# mx8m_cfg.net
KiCad netlist of a schematic drawn in Altium Designer
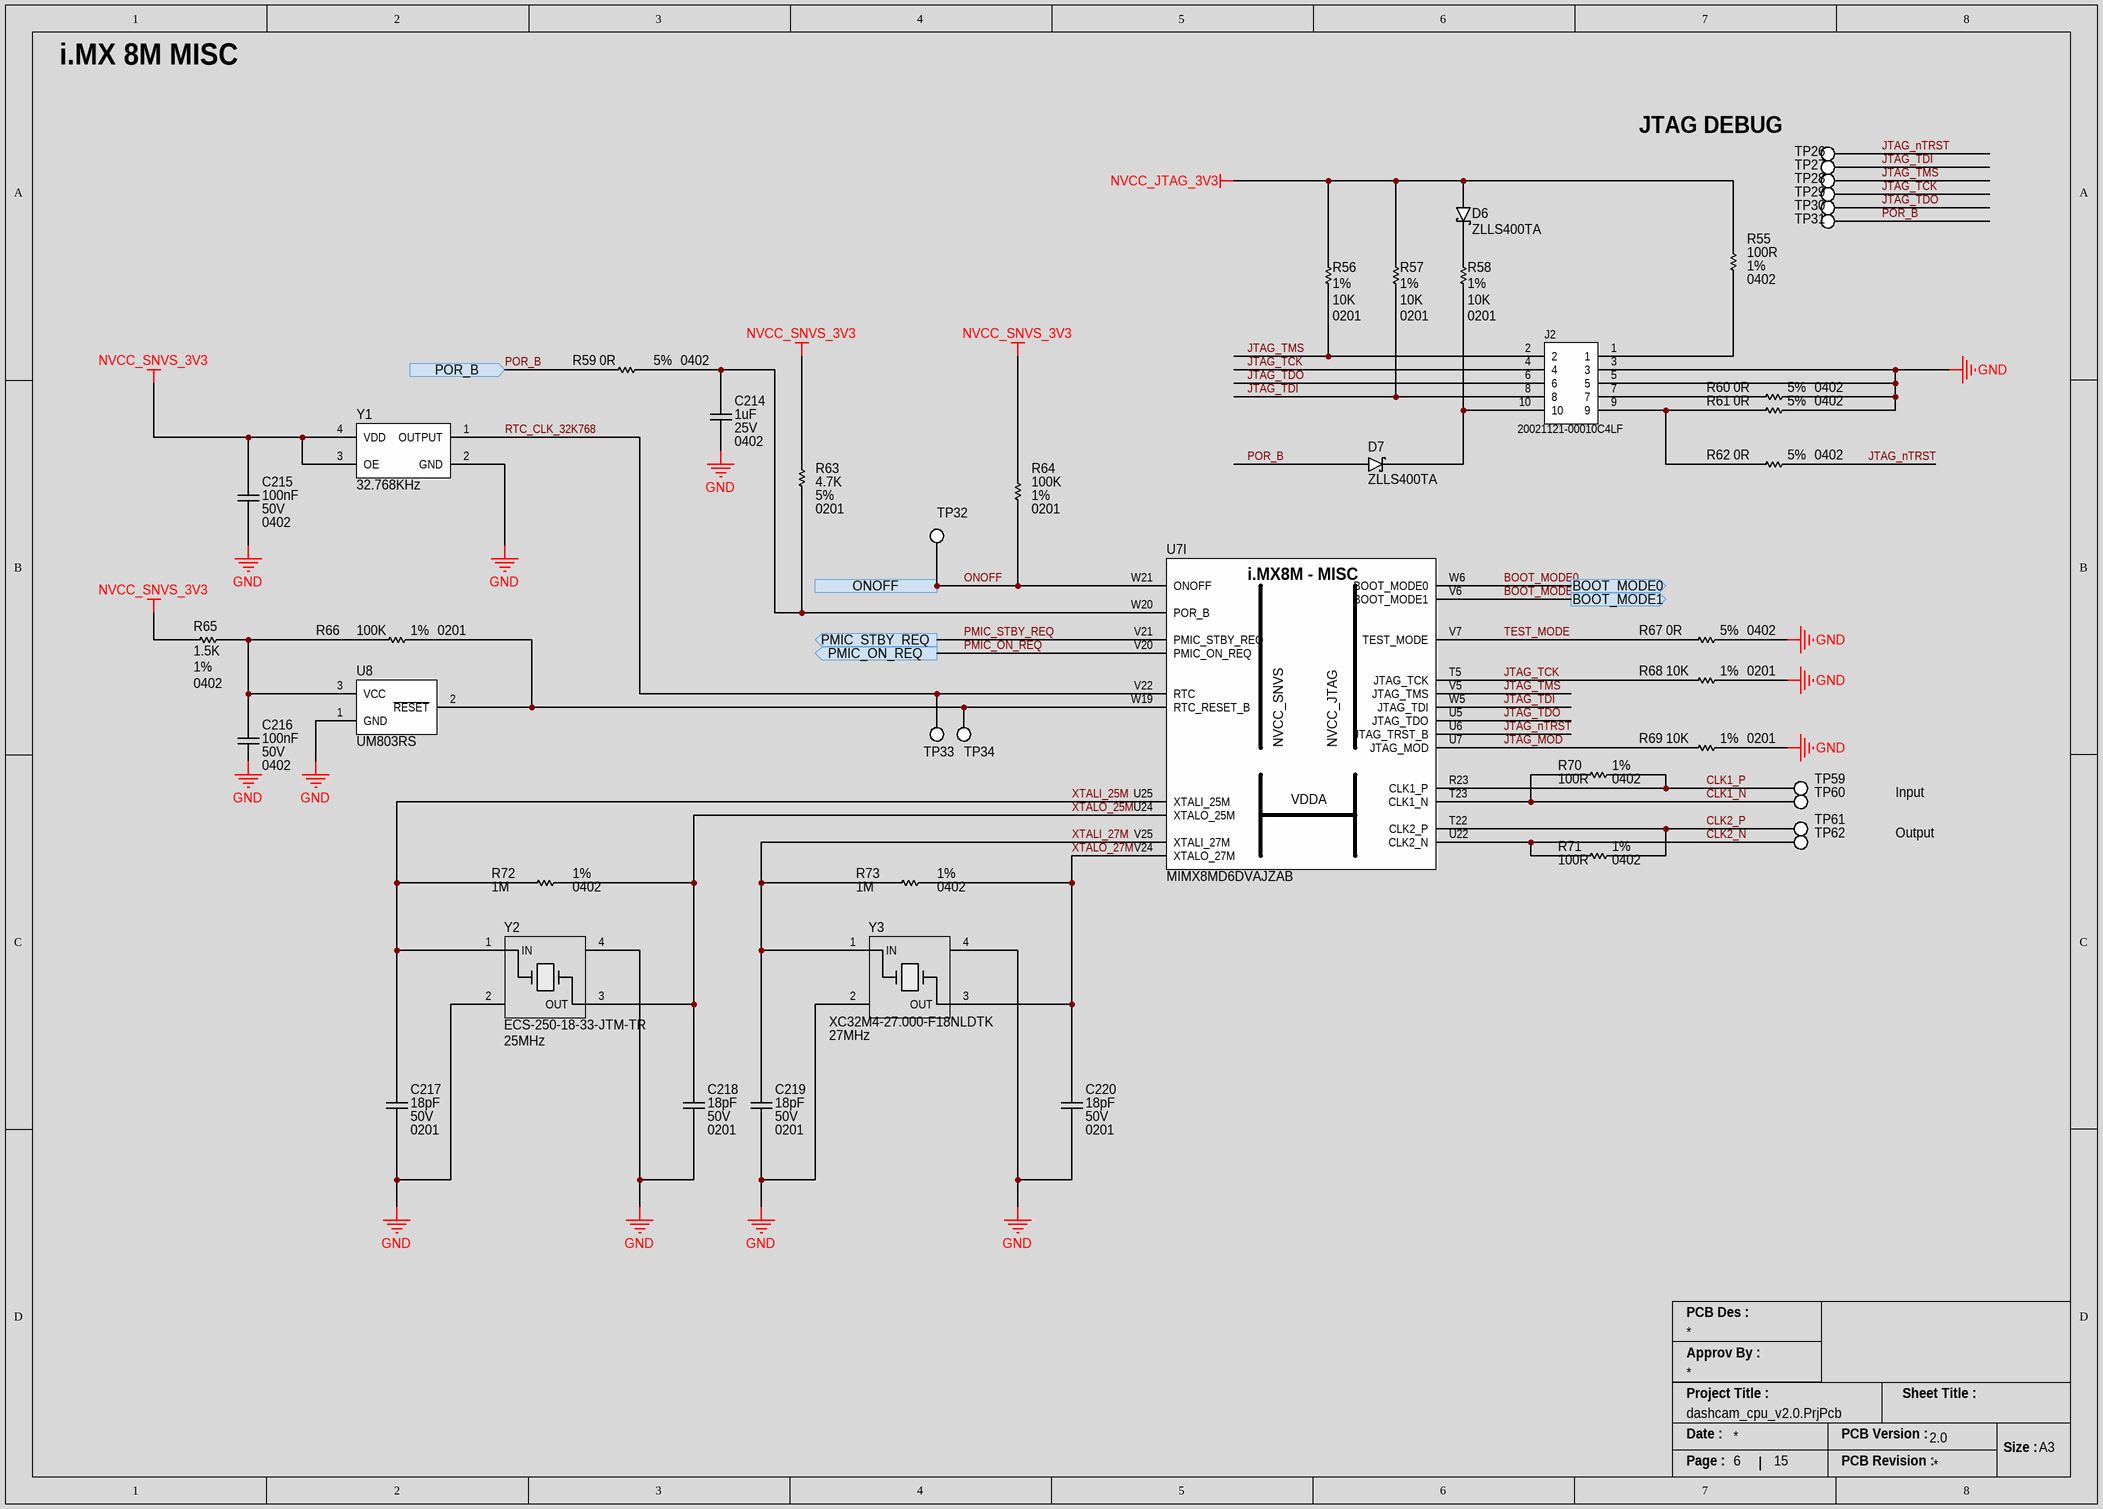
[diagram p0: mx8m_cfg.SchDoc]

(export (version "E")
  (design (tool "Eeschema 10.0.6"))
  (components
    (comp (ref "C214")
      (value "GRM155R61E105KA12D")
      (footprint "CAP_0402_CAPC1005X05N")
      (description "Multilayer Ceramic Capacitor, 1 uF, 25 V, ± 10%, X5R, 0402 [1005 Metric]")
      (fields
        (field (name "MANUFACTURER") "Murata")
        (field (name "TOLERANCE") "10%")
        (field (name "VOLTAGE RATING") "25V")
        (field (name "CAPACITANCE") "1uF")
        (field (name "CASE CODE (IMPERIAL)") "0402")
      )
      (libsource (lib "Electronic Devices_LIB") (part "CAP_1UF_25V_X5R_0402"))
    )
    (comp (ref "C215")
      (value "GRM155R71H104KE14D")
      (footprint "CAP_0402_CAPC1005X05N")
      (description "Multilayer Ceramic Capacitor, 0.1 uF, 16 V, ± 10%, X7R, 0402 [1005 Metric]")
      (fields
        (field (name "MANUFACTURER") "Murata")
        (field (name "TOLERANCE") "10%")
        (field (name "VOLTAGE RATING") "50V")
        (field (name "CAPACITANCE") "100nF")
        (field (name "CASE/PACKAGE") "0402")
      )
      (libsource (lib "Electronic Devices_LIB") (part "CAP_100NF_50V_X7R_0402"))
    )
    (comp (ref "C216")
      (value "GRM155R71H104KE14D")
      (footprint "CAP_0402_CAPC1005X05N")
      (description "Multilayer Ceramic Capacitor, 0.1 uF, 16 V, ± 10%, X7R, 0402 [1005 Metric]")
      (fields
        (field (name "MANUFACTURER") "Murata")
        (field (name "TOLERANCE") "10%")
        (field (name "VOLTAGE RATING") "50V")
        (field (name "CAPACITANCE") "100nF")
        (field (name "CASE/PACKAGE") "0402")
      )
      (libsource (lib "Electronic Devices_LIB") (part "CAP_100NF_50V_X7R_0402"))
    )
    (comp (ref "C217")
      (value "GRM0335C1H180JA01D")
      (footprint "CAP_0201_CAPC0603X03N")
      (description "Multilayer Ceramic Capacitor, 18 pF, 50 V, ± 5%, C0G (NP0), 0201 [0603 Metric]")
      (fields
        (field (name "MANUFACTURER") "Murata")
        (field (name "TOLERANCE") "5%")
        (field (name "CAPACITANCE") "18pF")
        (field (name "VOLTAGE RATING") "50V")
        (field (name "CASE/PACKAGE") "0201")
      )
      (libsource (lib "Electronic Devices_LIB") (part "CAP_18PF_50V_NP0_0201"))
    )
    (comp (ref "C218")
      (value "GRM0335C1H180JA01D")
      (footprint "CAP_0201_CAPC0603X03N")
      (description "Multilayer Ceramic Capacitor, 18 pF, 50 V, ± 5%, C0G (NP0), 0201 [0603 Metric]")
      (fields
        (field (name "MANUFACTURER") "Murata")
        (field (name "TOLERANCE") "5%")
        (field (name "CAPACITANCE") "18pF")
        (field (name "VOLTAGE RATING") "50V")
        (field (name "CASE/PACKAGE") "0201")
      )
      (libsource (lib "Electronic Devices_LIB") (part "CAP_18PF_50V_NP0_0201"))
    )
    (comp (ref "C219")
      (value "GRM0335C1H180JA01D")
      (footprint "CAP_0201_CAPC0603X03N")
      (description "Multilayer Ceramic Capacitor, 18 pF, 50 V, ± 5%, C0G (NP0), 0201 [0603 Metric]")
      (fields
        (field (name "MANUFACTURER") "Murata")
        (field (name "TOLERANCE") "5%")
        (field (name "CAPACITANCE") "18pF")
        (field (name "VOLTAGE RATING") "50V")
        (field (name "CASE/PACKAGE") "0201")
      )
      (libsource (lib "Electronic Devices_LIB") (part "CAP_18PF_50V_NP0_0201"))
    )
    (comp (ref "C220")
      (value "GRM0335C1H180JA01D")
      (footprint "CAP_0201_CAPC0603X03N")
      (description "Multilayer Ceramic Capacitor, 18 pF, 50 V, ± 5%, C0G (NP0), 0201 [0603 Metric]")
      (fields
        (field (name "MANUFACTURER") "Murata")
        (field (name "TOLERANCE") "5%")
        (field (name "CAPACITANCE") "18pF")
        (field (name "VOLTAGE RATING") "50V")
        (field (name "CASE/PACKAGE") "0201")
      )
      (libsource (lib "Electronic Devices_LIB") (part "CAP_18PF_50V_NP0_0201"))
    )
    (comp (ref "D6")
      (value "ZLLS400TA")
      (footprint "DIO_SOD2512X113N")
      (description "DIODE SCHOTTKY 40V 520MA SOD323")
      (fields (field (name "MANUFACTURER") "Diodes Zetex"))
      (libsource (lib "Electronic Devices_LIB") (part "DIO_SCTKY_40V_520mA_ZLLS400TA"))
    )
    (comp (ref "D7")
      (value "ZLLS400TA")
      (footprint "DIO_SOD2512X113N")
      (description "DIODE SCHOTTKY 40V 520MA SOD323")
      (fields (field (name "MANUFACTURER") "Diodes Zetex"))
      (libsource (lib "Electronic Devices_LIB") (part "DIO_SCTKY_40V_520mA_ZLLS400TA"))
    )
    (comp (ref "J2")
      (value "20021121-00010C4LF")
      (footprint "CONN_HDR_MALE_10P_2R")
      (description "Conn Unshrouded Header HDR 10 POS 1.27mm Solder ST Top Entry SMD Minitek127® T/R")
      (fields (field (name "MANUFACTURER") "Amphenol ICC / FCI"))
      (libsource (lib "Electronic Devices_LIB") (part "CONN_HEADER_MALE_10P_2R_1.27MM"))
    )
    (comp (ref "R55")
      (value "ERJ-2RKF1000X")
      (footprint "RES_0402_RESC1005X04N")
      (description "Resistor Thick Film 0402 100 Ohm 1% 1/10W 100ppm/C Molded SMD Punched Carrier T/R")
      (fields
        (field (name "MANUFACTURER") "Panasonic")
        (field (name "TOLERANCE") "1%")
        (field (name "RESISTANCE") "100R")
        (field (name "CASE/PACKAGE") "0402")
      )
      (libsource (lib "Electronic Devices_LIB") (part "RES_100R_1%_100mW_0402"))
    )
    (comp (ref "R56")
      (value "RC0201FR-0710KL")
      (footprint "RES_0201_RESC0603X02N")
      (description "SMD Chip Resistor, 10 kOhm, ± 1%, 50 mW, 0201 [0603 Metric], Thick Film, General Purpose")
      (fields
        (field (name "MANUFACTURER") "Yageo")
        (field (name "TOLERANCE") "1%")
        (field (name "RESISTANCE") "10K")
        (field (name "CASE CODE (IMPERIAL)") "0201")
      )
      (libsource (lib "Electronic Devices_LIB") (part "RES_10K_1/12W_1%_0201"))
    )
    (comp (ref "R57")
      (value "RC0201FR-0710KL")
      (footprint "RES_0201_RESC0603X02N")
      (description "SMD Chip Resistor, 10 kOhm, ± 1%, 50 mW, 0201 [0603 Metric], Thick Film, General Purpose")
      (fields
        (field (name "MANUFACTURER") "Yageo")
        (field (name "TOLERANCE") "1%")
        (field (name "RESISTANCE") "10K")
        (field (name "CASE CODE (IMPERIAL)") "0201")
      )
      (libsource (lib "Electronic Devices_LIB") (part "RES_10K_1/12W_1%_0201"))
    )
    (comp (ref "R58")
      (value "RC0201FR-0710KL")
      (footprint "RES_0201_RESC0603X02N")
      (description "SMD Chip Resistor, 10 kOhm, ± 1%, 50 mW, 0201 [0603 Metric], Thick Film, General Purpose")
      (fields
        (field (name "MANUFACTURER") "Yageo")
        (field (name "TOLERANCE") "1%")
        (field (name "RESISTANCE") "10K")
        (field (name "CASE CODE (IMPERIAL)") "0201")
      )
      (libsource (lib "Electronic Devices_LIB") (part "RES_10K_1/12W_1%_0201"))
    )
    (comp (ref "R59")
      (value "ERJ-2GE0R00X")
      (footprint "RES_0402_RESC1005X04N")
      (description "SMD Chip Resistor, Jumper, 0 ohm, 100 mW, 0402 [1005 Metric], Thick Film, General Purpose")
      (fields
        (field (name "MANUFACTURER") "Panasonic")
        (field (name "CASE CODE (IMPERIAL)") "0402")
        (field (name "TOLERANCE") "5%")
        (field (name "RESISTANCE") "0R")
      )
      (libsource (lib "Electronic Devices_LIB") (part "RES_0R_5%_100mW_0402"))
    )
    (comp (ref "R60")
      (value "ERJ-2GE0R00X")
      (footprint "RES_0402_RESC1005X04N")
      (description "SMD Chip Resistor, Jumper, 0 ohm, 100 mW, 0402 [1005 Metric], Thick Film, General Purpose")
      (fields
        (field (name "MANUFACTURER") "Panasonic")
        (field (name "CASE CODE (IMPERIAL)") "0402")
        (field (name "TOLERANCE") "5%")
        (field (name "RESISTANCE") "0R")
      )
      (libsource (lib "Electronic Devices_LIB") (part "RES_0R_5%_100mW_0402"))
    )
    (comp (ref "R61")
      (value "ERJ-2GE0R00X")
      (footprint "RES_0402_RESC1005X04N")
      (description "SMD Chip Resistor, Jumper, 0 ohm, 100 mW, 0402 [1005 Metric], Thick Film, General Purpose")
      (fields
        (field (name "MANUFACTURER") "Panasonic")
        (field (name "CASE CODE (IMPERIAL)") "0402")
        (field (name "TOLERANCE") "5%")
        (field (name "RESISTANCE") "0R")
      )
      (libsource (lib "Electronic Devices_LIB") (part "RES_0R_5%_100mW_0402"))
    )
    (comp (ref "R62")
      (value "ERJ-2GE0R00X")
      (footprint "RES_0402_RESC1005X04N")
      (description "SMD Chip Resistor, Jumper, 0 ohm, 100 mW, 0402 [1005 Metric], Thick Film, General Purpose")
      (fields
        (field (name "MANUFACTURER") "Panasonic")
        (field (name "CASE CODE (IMPERIAL)") "0402")
        (field (name "TOLERANCE") "5%")
        (field (name "RESISTANCE") "0R")
      )
      (libsource (lib "Electronic Devices_LIB") (part "RES_0R_5%_100mW_0402"))
    )
    (comp (ref "R63")
      (value "RK73B1HTTC472J")
      (footprint "RES_0201_RESC0603X02N")
      (description "Res Thick Film 0201 4.7K Ohm 5% 0.05W(1/20W) ±200ppm/C Pad SMD Automotive T/R")
      (fields
        (field (name "MANUFACTURER") "KOA Speer")
        (field (name "TOLERANCE") "5%")
        (field (name "RESISTANCE") "4.7K")
        (field (name "CASE/PACKAGE") "0201")
      )
      (libsource (lib "Electronic Devices_LIB") (part "RES_4.7K_5%_50mW_0201"))
    )
    (comp (ref "R64")
      (value "RC0201FR-07100KL")
      (footprint "RES_0201_RESC0603X02N")
      (description "SMD Chip Resistor, 100 kOhm, ± 1%, 50 mW, 0201 [0603 Metric], Thick Film, General Purpose")
      (fields
        (field (name "MANUFACTURER") "Yageo")
        (field (name "RESISTANCE") "100K")
        (field (name "TOLERANCE") "1%")
        (field (name "CASE/PACKAGE") "0201")
      )
      (libsource (lib "Electronic Devices_LIB") (part "RES_100K_1%_50mW_0201"))
    )
    (comp (ref "R65")
      (value "CR0402-FX-1501GLF")
      (footprint "RES_0402_RESC1005X04N")
      (description "Res Thick Film 0402 1.5K Ohm 1% 1/16W ±100ppm/°C Molded SMD SMD Paper Tape on Plastic Reel")
      (fields
        (field (name "MANUFACTURER") "Bourns")
        (field (name "RESISTANCE") "1.5K")
        (field (name "TOLERANCE") "1%")
        (field (name "CASE/PACKAGE") "0402")
      )
      (libsource (lib "Electronic Devices_LIB") (part "RES_1.5K_1%_63mW_0402"))
    )
    (comp (ref "R66")
      (value "RC0201FR-07100KL")
      (footprint "RES_0201_RESC0603X02N")
      (description "SMD Chip Resistor, 100 kOhm, ± 1%, 50 mW, 0201 [0603 Metric], Thick Film, General Purpose")
      (fields
        (field (name "MANUFACTURER") "Yageo")
        (field (name "RESISTANCE") "100K")
        (field (name "TOLERANCE") "1%")
        (field (name "CASE/PACKAGE") "0201")
      )
      (libsource (lib "Electronic Devices_LIB") (part "RES_100K_1%_50mW_0201"))
    )
    (comp (ref "R67")
      (value "ERJ-2GE0R00X")
      (footprint "RES_0402_RESC1005X04N")
      (description "SMD Chip Resistor, Jumper, 0 ohm, 100 mW, 0402 [1005 Metric], Thick Film, General Purpose")
      (fields
        (field (name "MANUFACTURER") "Panasonic")
        (field (name "CASE CODE (IMPERIAL)") "0402")
        (field (name "TOLERANCE") "5%")
        (field (name "RESISTANCE") "0R")
      )
      (libsource (lib "Electronic Devices_LIB") (part "RES_0R_5%_100mW_0402"))
    )
    (comp (ref "R68")
      (value "RC0201FR-0710KL")
      (footprint "RES_0201_RESC0603X02N")
      (description "SMD Chip Resistor, 10 kOhm, ± 1%, 50 mW, 0201 [0603 Metric], Thick Film, General Purpose")
      (fields
        (field (name "MANUFACTURER") "Yageo")
        (field (name "TOLERANCE") "1%")
        (field (name "RESISTANCE") "10K")
        (field (name "CASE CODE (IMPERIAL)") "0201")
      )
      (libsource (lib "Electronic Devices_LIB") (part "RES_10K_1/12W_1%_0201"))
    )
    (comp (ref "R69")
      (value "RC0201FR-0710KL")
      (footprint "RES_0201_RESC0603X02N")
      (description "SMD Chip Resistor, 10 kOhm, ± 1%, 50 mW, 0201 [0603 Metric], Thick Film, General Purpose")
      (fields
        (field (name "MANUFACTURER") "Yageo")
        (field (name "TOLERANCE") "1%")
        (field (name "RESISTANCE") "10K")
        (field (name "CASE CODE (IMPERIAL)") "0201")
      )
      (libsource (lib "Electronic Devices_LIB") (part "RES_10K_1/12W_1%_0201"))
    )
    (comp (ref "R70")
      (value "ERJ-2RKF1000X")
      (footprint "RES_0402_RESC1005X04N")
      (description "Resistor Thick Film 0402 100 Ohm 1% 1/10W 100ppm/C Molded SMD Punched Carrier T/R")
      (fields
        (field (name "MANUFACTURER") "Panasonic")
        (field (name "TOLERANCE") "1%")
        (field (name "RESISTANCE") "100R")
        (field (name "CASE/PACKAGE") "0402")
      )
      (libsource (lib "Electronic Devices_LIB") (part "RES_100R_1%_100mW_0402"))
    )
    (comp (ref "R71")
      (value "ERJ-2RKF1000X")
      (footprint "RES_0402_RESC1005X04N")
      (description "Resistor Thick Film 0402 100 Ohm 1% 1/10W 100ppm/C Molded SMD Punched Carrier T/R")
      (fields
        (field (name "MANUFACTURER") "Panasonic")
        (field (name "TOLERANCE") "1%")
        (field (name "RESISTANCE") "100R")
        (field (name "CASE/PACKAGE") "0402")
      )
      (libsource (lib "Electronic Devices_LIB") (part "RES_100R_1%_100mW_0402"))
    )
    (comp (ref "R72")
      (value "CR0402-FX-1004GLF")
      (footprint "RES_0402_RESC1005X04N")
      (description "Res Thick Film 0402 1M Ohm 1% 1/16W ±100ppm/°C Molded SMD SMD Paper Tape on Plastic Reel")
      (fields
        (field (name "MANUFACTURER") "Bourns")
        (field (name "RESISTANCE") "1M")
        (field (name "TOLERANCE") "1%")
        (field (name "CASE/PACKAGE") "0402")
      )
      (libsource (lib "Electronic Devices_LIB") (part "RES_1M_1%_63mW_0402"))
    )
    (comp (ref "R73")
      (value "CR0402-FX-1004GLF")
      (footprint "RES_0402_RESC1005X04N")
      (description "Res Thick Film 0402 1M Ohm 1% 1/16W ±100ppm/°C Molded SMD SMD Paper Tape on Plastic Reel")
      (fields
        (field (name "MANUFACTURER") "Bourns")
        (field (name "RESISTANCE") "1M")
        (field (name "TOLERANCE") "1%")
        (field (name "CASE/PACKAGE") "0402")
      )
      (libsource (lib "Electronic Devices_LIB") (part "RES_1M_1%_63mW_0402"))
    )
    (comp (ref "TP26")
      (value "NO COMPONENT")
      (footprint "TP_PAD_1.6MM_SMD_ROUND")
      (description "Test Point, SMD pad, round, 1.5mm, 1.6mm, 3mm diameter")
      (libsource (lib "Electronic Devices_LIB") (part "TP_PAD_SMD_Round"))
    )
    (comp (ref "TP27")
      (value "NO COMPONENT")
      (footprint "TP_PAD_1.6MM_SMD_ROUND")
      (description "Test Point, SMD pad, round, 1.5mm, 1.6mm, 3mm diameter")
      (libsource (lib "Electronic Devices_LIB") (part "TP_PAD_SMD_Round"))
    )
    (comp (ref "TP28")
      (value "NO COMPONENT")
      (footprint "TP_PAD_1.6MM_SMD_ROUND")
      (description "Test Point, SMD pad, round, 1.5mm, 1.6mm, 3mm diameter")
      (libsource (lib "Electronic Devices_LIB") (part "TP_PAD_SMD_Round"))
    )
    (comp (ref "TP29")
      (value "NO COMPONENT")
      (footprint "TP_PAD_1.6MM_SMD_ROUND")
      (description "Test Point, SMD pad, round, 1.5mm, 1.6mm, 3mm diameter")
      (libsource (lib "Electronic Devices_LIB") (part "TP_PAD_SMD_Round"))
    )
    (comp (ref "TP30")
      (value "NO COMPONENT")
      (footprint "TP_PAD_1.6MM_SMD_ROUND")
      (description "Test Point, SMD pad, round, 1.5mm, 1.6mm, 3mm diameter")
      (libsource (lib "Electronic Devices_LIB") (part "TP_PAD_SMD_Round"))
    )
    (comp (ref "TP31")
      (value "NO COMPONENT")
      (footprint "TP_PAD_1.6MM_SMD_ROUND")
      (description "Test Point, SMD pad, round, 1.5mm, 1.6mm, 3mm diameter")
      (libsource (lib "Electronic Devices_LIB") (part "TP_PAD_SMD_Round"))
    )
    (comp (ref "TP32")
      (value "NO COMPONENT")
      (footprint "TP_PAD_1.6MM_SMD_ROUND")
      (description "Test Point, SMD pad, round, 1.5mm, 1.6mm, 3mm diameter")
      (libsource (lib "Electronic Devices_LIB") (part "TP_PAD_SMD_Round"))
    )
    (comp (ref "TP33")
      (value "NO COMPONENT")
      (footprint "TP_PAD_1.6MM_SMD_ROUND")
      (description "Test Point, SMD pad, round, 1.5mm, 1.6mm, 3mm diameter")
      (libsource (lib "Electronic Devices_LIB") (part "TP_PAD_SMD_Round"))
    )
    (comp (ref "TP34")
      (value "NO COMPONENT")
      (footprint "TP_PAD_1.6MM_SMD_ROUND")
      (description "Test Point, SMD pad, round, 1.5mm, 1.6mm, 3mm diameter")
      (libsource (lib "Electronic Devices_LIB") (part "TP_PAD_SMD_Round"))
    )
    (comp (ref "TP59")
      (value "NO COMPONENT")
      (footprint "TP_PAD_1.6MM_SMD_ROUND")
      (description "Test Point, SMD pad, round, 1.5mm, 1.6mm, 3mm diameter")
      (libsource (lib "Electronic Devices_LIB") (part "TP_PAD_SMD_Round"))
    )
    (comp (ref "TP60")
      (value "NO COMPONENT")
      (footprint "TP_PAD_1.6MM_SMD_ROUND")
      (description "Test Point, SMD pad, round, 1.5mm, 1.6mm, 3mm diameter")
      (libsource (lib "Electronic Devices_LIB") (part "TP_PAD_SMD_Round"))
    )
    (comp (ref "TP61")
      (value "NO COMPONENT")
      (footprint "TP_PAD_1.6MM_SMD_ROUND")
      (description "Test Point, SMD pad, round, 1.5mm, 1.6mm, 3mm diameter")
      (libsource (lib "Electronic Devices_LIB") (part "TP_PAD_SMD_Round"))
    )
    (comp (ref "TP62")
      (value "NO COMPONENT")
      (footprint "TP_PAD_1.6MM_SMD_ROUND")
      (description "Test Point, SMD pad, round, 1.5mm, 1.6mm, 3mm diameter")
      (libsource (lib "Electronic Devices_LIB") (part "TP_PAD_SMD_Round"))
    )
    (comp (ref "U7")
      (value "MIMX8MD6DVAJZAB")
      (footprint "IC_MPU_BGA621C65P25X25_1700X1700X218")
      (fields (field (name "MANUFACTURER") "NXP Semiconductors"))
      (libsource (lib "Electronic Devices_LIB") (part "IC_MPU_ARM_1.5GHZ_MIMX8MD6DVAJZAB"))
    )
    (comp (ref "U8")
      (value "UM803RS")
      (footprint "IC_SUP_VOL_UM805RS")
      (description "3-Pin Microprocessor Reset Circuits")
      (fields (field (name "MANUFACTURER") "Union Semiconductor"))
      (libsource (lib "Electronic Devices_LIB") (part "IC_VOLTAGE_SUPERVISOR_UM803RS"))
    )
    (comp (ref "Y1")
      (value "ASH7KW-32.768kHz-L-T")
      (footprint "CRYSTAL_32.768KHZ_ASH7KW32768kHzLT")
      (description "OSC XO 32.768KHZ CMOS SMD")
      (fields (field (name "MANUFACTURER") "Abracon") (field (name "FREQUENCY") "32.768KHz"))
      (libsource (lib "Electronic Devices_LIB") (part "CRYSTAL_ABRACON_32.768KHZ"))
    )
    (comp (ref "Y2")
      (value "ECS-250-18-33-JTM-TR")
      (footprint "CRYSTAL_ECS-250-18-33-JTM-TR")
      (description "Crystal 25MHz ±20ppm (Tol) ±20ppm (Stability) 18pF FUND 40Ohm 4-Pin Mini-CSMD T/R")
      (fields (field (name "MANUFACTURER") "ECS International") (field (name "FREQUENCY") "25MHz"))
      (libsource (lib "Electronic Devices_LIB") (part "CRYSTAL_ECS_25MHZ_ECS-250-18-33-JTM-TR"))
    )
    (comp (ref "Y3")
      (value "XC32M4-27.000-F18NLDTK")
      (footprint "CRYSTAL_ECS-250-18-33-JTM-TR")
      (description "27 MHz ±20ppm Crystal 18pF 40 Ohms 4-SMD, No Lead")
      (fields
        (field (name "MANUFACTURER") "Suzhou Hangjing Elec&Tech Co.,Ltd")
        (field (name "FREQUENCY") "27MHz")
      )
      (libsource (lib "Electronic Devices_LIB") (part "CRYSTAL_SUZHOU_27MHz_XC32M4-27.000-F18NLDTK"))
    )
  )
  (nets
    (net (code "1") (name "/BOOT_MODE0") (class "Default")
      (node (ref "U7") (pin "W6") (pinfunction "BOOT_MODE0_W6") (pintype "passive"))
    )
    (net (code "2") (name "/BOOT_MODE1") (class "Default")
      (node (ref "U7") (pin "V6") (pinfunction "BOOT_MODE1_V6") (pintype "passive"))
    )
    (net (code "3") (name "/CLK1_N") (class "Default")
      (node (ref "R70") (pin "1") (pinfunction "1_1") (pintype "passive"))
      (node (ref "TP60") (pin "1") (pinfunction "1_1") (pintype "passive"))
      (node (ref "U7") (pin "T23") (pinfunction "CLK1_N_T23") (pintype "passive"))
    )
    (net (code "4") (name "/CLK1_P") (class "Default")
      (node (ref "R70") (pin "2") (pinfunction "2_2") (pintype "passive"))
      (node (ref "TP59") (pin "1") (pinfunction "1_1") (pintype "passive"))
      (node (ref "U7") (pin "R23") (pinfunction "CLK1_P_R23") (pintype "passive"))
    )
    (net (code "5") (name "/CLK2_N") (class "Default")
      (node (ref "R71") (pin "1") (pinfunction "1_1") (pintype "passive"))
      (node (ref "TP62") (pin "1") (pinfunction "1_1") (pintype "passive"))
      (node (ref "U7") (pin "U22") (pinfunction "CLK2_N_U22") (pintype "passive"))
    )
    (net (code "6") (name "/CLK2_P") (class "Default")
      (node (ref "R71") (pin "2") (pinfunction "2_2") (pintype "passive"))
      (node (ref "TP61") (pin "1") (pinfunction "1_1") (pintype "passive"))
      (node (ref "U7") (pin "T22") (pinfunction "CLK2_P_T22") (pintype "passive"))
    )
    (net (code "7") (name "/JTAG_MOD") (class "Default")
      (node (ref "R69") (pin "1") (pinfunction "1_1") (pintype "passive"))
      (node (ref "U7") (pin "U7") (pinfunction "JTAG_MOD_U7") (pintype "passive"))
    )
    (net (code "8") (name "/JTAG_TCK") (class "Default")
      (node (ref "J2") (pin "4") (pinfunction "4_4") (pintype "passive"))
      (node (ref "R68") (pin "1") (pinfunction "1_1") (pintype "passive"))
      (node (ref "TP29") (pin "1") (pinfunction "1_1") (pintype "passive"))
      (node (ref "U7") (pin "T5") (pinfunction "JTAG_TCK_T5") (pintype "passive"))
    )
    (net (code "9") (name "/JTAG_TDI") (class "Default")
      (node (ref "J2") (pin "8") (pinfunction "8_8") (pintype "passive"))
      (node (ref "R57") (pin "1") (pinfunction "1_1") (pintype "passive"))
      (node (ref "TP27") (pin "1") (pinfunction "1_1") (pintype "passive"))
      (node (ref "U7") (pin "W5") (pinfunction "JTAG_TDI_W5") (pintype "passive"))
    )
    (net (code "10") (name "/JTAG_TDO") (class "Default")
      (node (ref "J2") (pin "6") (pinfunction "6_6") (pintype "passive"))
      (node (ref "TP30") (pin "1") (pinfunction "1_1") (pintype "passive"))
      (node (ref "U7") (pin "U5") (pinfunction "JTAG_TDO_U5") (pintype "passive"))
    )
    (net (code "11") (name "/JTAG_TMS") (class "Default")
      (node (ref "J2") (pin "2") (pinfunction "2_2") (pintype "passive"))
      (node (ref "R56") (pin "1") (pinfunction "1_1") (pintype "passive"))
      (node (ref "TP28") (pin "1") (pinfunction "1_1") (pintype "passive"))
      (node (ref "U7") (pin "V5") (pinfunction "JTAG_TMS_V5") (pintype "passive"))
    )
    (net (code "12") (name "/JTAG_nTRST") (class "Default")
      (node (ref "R62") (pin "2") (pinfunction "2_2") (pintype "passive"))
      (node (ref "TP26") (pin "1") (pinfunction "1_1") (pintype "passive"))
      (node (ref "U7") (pin "U6") (pinfunction "JTAG_TRST_B_U6") (pintype "passive"))
    )
    (net (code "13") (name "/ONOFF") (class "Default")
      (node (ref "R64") (pin "1") (pinfunction "1_1") (pintype "passive"))
      (node (ref "TP32") (pin "1") (pinfunction "1_1") (pintype "passive"))
      (node (ref "U7") (pin "W21") (pinfunction "ONOFF_W21") (pintype "passive"))
    )
    (net (code "14") (name "/PMIC_ON_REQ") (class "Default")
      (node (ref "U7") (pin "V20") (pinfunction "PMIC_ON_REQ_V20") (pintype "passive"))
    )
    (net (code "15") (name "/PMIC_STBY_REQ") (class "Default")
      (node (ref "U7") (pin "V21") (pinfunction "PMIC_STBY_REQ_V21") (pintype "passive"))
    )
    (net (code "16") (name "/POR_B") (class "Default")
      (node (ref "D7") (pin "2") (pinfunction "A_2") (pintype "passive"))
      (node (ref "R59") (pin "1") (pinfunction "1_1") (pintype "passive"))
      (node (ref "TP31") (pin "1") (pinfunction "1_1") (pintype "passive"))
    )
    (net (code "17") (name "/RTC_CLK_32K768") (class "Default")
      (node (ref "TP33") (pin "1") (pinfunction "1_1") (pintype "passive"))
      (node (ref "U7") (pin "V22") (pinfunction "RTC_V22") (pintype "passive"))
      (node (ref "Y1") (pin "1") (pinfunction "OUTPUT_1") (pintype "passive"))
    )
    (net (code "18") (name "/TEST_MODE") (class "Default")
      (node (ref "R67") (pin "1") (pinfunction "1_1") (pintype "passive"))
      (node (ref "U7") (pin "V7") (pinfunction "TEST_MODE_V7") (pintype "passive"))
    )
    (net (code "19") (name "/XTALI_25M") (class "Default")
      (node (ref "C217") (pin "2") (pinfunction "2_2") (pintype "passive"))
      (node (ref "R72") (pin "1") (pinfunction "1_1") (pintype "passive"))
      (node (ref "U7") (pin "U25") (pinfunction "XTALI_25M_U25") (pintype "passive"))
      (node (ref "Y2") (pin "1") (pinfunction "IN_1") (pintype "passive"))
    )
    (net (code "20") (name "/XTALI_27M") (class "Default")
      (node (ref "C219") (pin "2") (pinfunction "2_2") (pintype "passive"))
      (node (ref "R73") (pin "1") (pinfunction "1_1") (pintype "passive"))
      (node (ref "U7") (pin "V25") (pinfunction "XTALI_27M_V25") (pintype "passive"))
      (node (ref "Y3") (pin "1") (pinfunction "IN_1") (pintype "passive"))
    )
    (net (code "21") (name "/XTALO_25M") (class "Default")
      (node (ref "C218") (pin "2") (pinfunction "2_2") (pintype "passive"))
      (node (ref "R72") (pin "2") (pinfunction "2_2") (pintype "passive"))
      (node (ref "U7") (pin "U24") (pinfunction "XTALO_25M_U24") (pintype "passive"))
      (node (ref "Y2") (pin "3") (pinfunction "OUT_3") (pintype "passive"))
    )
    (net (code "22") (name "/XTALO_27M") (class "Default")
      (node (ref "C220") (pin "2") (pinfunction "2_2") (pintype "passive"))
      (node (ref "R73") (pin "2") (pinfunction "2_2") (pintype "passive"))
      (node (ref "U7") (pin "V24") (pinfunction "XTALO_27M_V24") (pintype "passive"))
      (node (ref "Y3") (pin "3") (pinfunction "OUT_3") (pintype "passive"))
    )
    (net (code "23") (name "GND") (class "Default")
      (node (ref "C214") (pin "1") (pinfunction "1_1") (pintype "passive"))
      (node (ref "C215") (pin "1") (pinfunction "1_1") (pintype "passive"))
      (node (ref "C216") (pin "1") (pinfunction "1_1") (pintype "passive"))
      (node (ref "C217") (pin "1") (pinfunction "1_1") (pintype "passive"))
      (node (ref "C218") (pin "1") (pinfunction "1_1") (pintype "passive"))
      (node (ref "C219") (pin "1") (pinfunction "1_1") (pintype "passive"))
      (node (ref "C220") (pin "1") (pinfunction "1_1") (pintype "passive"))
      (node (ref "J2") (pin "3") (pinfunction "3_3") (pintype "passive"))
      (node (ref "J2") (pin "5") (pinfunction "5_5") (pintype "passive"))
      (node (ref "R60") (pin "2") (pinfunction "2_2") (pintype "passive"))
      (node (ref "R61") (pin "2") (pinfunction "2_2") (pintype "passive"))
      (node (ref "R67") (pin "2") (pinfunction "2_2") (pintype "passive"))
      (node (ref "R68") (pin "2") (pinfunction "2_2") (pintype "passive"))
      (node (ref "R69") (pin "2") (pinfunction "2_2") (pintype "passive"))
      (node (ref "U8") (pin "1") (pinfunction "GND_1") (pintype "passive"))
      (node (ref "Y1") (pin "2") (pinfunction "GND_2") (pintype "passive"))
      (node (ref "Y2") (pin "2") (pinfunction "2_2") (pintype "passive"))
      (node (ref "Y2") (pin "4") (pinfunction "4_4") (pintype "passive"))
      (node (ref "Y3") (pin "2") (pinfunction "2_2") (pintype "passive"))
      (node (ref "Y3") (pin "4") (pinfunction "4_4") (pintype "passive"))
    )
    (net (code "24") (name "NVCC_JTAG_3V3") (class "Default")
      (node (ref "D6") (pin "2") (pinfunction "A_2") (pintype "passive"))
      (node (ref "R55") (pin "2") (pinfunction "2_2") (pintype "passive"))
      (node (ref "R56") (pin "2") (pinfunction "2_2") (pintype "passive"))
      (node (ref "R57") (pin "2") (pinfunction "2_2") (pintype "passive"))
    )
    (net (code "25") (name "NVCC_SNVS_3V3") (class "Default")
      (node (ref "C215") (pin "2") (pinfunction "2_2") (pintype "passive"))
      (node (ref "R63") (pin "2") (pinfunction "2_2") (pintype "passive"))
      (node (ref "R64") (pin "2") (pinfunction "2_2") (pintype "passive"))
      (node (ref "R65") (pin "2") (pinfunction "2_2") (pintype "passive"))
      (node (ref "Y1") (pin "3") (pinfunction "OE_3") (pintype "passive"))
      (node (ref "Y1") (pin "4") (pinfunction "VDD_4") (pintype "passive"))
    )
    (net (code "26") (name "Net-(D6-K)") (class "Default")
      (node (ref "D6") (pin "1") (pinfunction "K_1") (pintype "passive"))
      (node (ref "R58") (pin "2") (pinfunction "2_2") (pintype "passive"))
    )
    (net (code "27") (name "Net-(D7-K)") (class "Default")
      (node (ref "D7") (pin "1") (pinfunction "K_1") (pintype "passive"))
      (node (ref "J2") (pin "10") (pinfunction "10_10") (pintype "passive"))
      (node (ref "R58") (pin "1") (pinfunction "1_1") (pintype "passive"))
    )
    (net (code "28") (name "Net-(J2-Pad1)") (class "Default")
      (node (ref "J2") (pin "1") (pinfunction "1_1") (pintype "passive"))
      (node (ref "R55") (pin "1") (pinfunction "1_1") (pintype "passive"))
    )
    (net (code "29") (name "Net-(J2-Pad7)") (class "Default")
      (node (ref "J2") (pin "7") (pinfunction "7_7") (pintype "passive"))
      (node (ref "R60") (pin "1") (pinfunction "1_1") (pintype "passive"))
    )
    (net (code "30") (name "Net-(J2-Pad9)") (class "Default")
      (node (ref "J2") (pin "9") (pinfunction "9_9") (pintype "passive"))
      (node (ref "R61") (pin "1") (pinfunction "1_1") (pintype "passive"))
      (node (ref "R62") (pin "1") (pinfunction "1_1") (pintype "passive"))
    )
    (net (code "31") (name "Net-(U7I-POR_B)") (class "Default")
      (node (ref "C214") (pin "2") (pinfunction "2_2") (pintype "passive"))
      (node (ref "R59") (pin "2") (pinfunction "2_2") (pintype "passive"))
      (node (ref "R63") (pin "1") (pinfunction "1_1") (pintype "passive"))
      (node (ref "U7") (pin "W20") (pinfunction "POR_B_W20") (pintype "passive"))
    )
    (net (code "32") (name "Net-(U7I-RTC_RESET_B)") (class "Default")
      (node (ref "R66") (pin "2") (pinfunction "2_2") (pintype "passive"))
      (node (ref "TP34") (pin "1") (pinfunction "1_1") (pintype "passive"))
      (node (ref "U7") (pin "W19") (pinfunction "RTC_RESET_B_W19") (pintype "passive"))
      (node (ref "U8") (pin "2") (pinfunction "~{RESET}_2") (pintype "passive"))
    )
    (net (code "33") (name "Net-(U8-VCC)") (class "Default")
      (node (ref "C216") (pin "2") (pinfunction "2_2") (pintype "passive"))
      (node (ref "R65") (pin "1") (pinfunction "1_1") (pintype "passive"))
      (node (ref "R66") (pin "1") (pinfunction "1_1") (pintype "passive"))
      (node (ref "U8") (pin "3") (pinfunction "VCC_3") (pintype "passive"))
    )
  )
)
